# deck.net
KiCad netlist of a schematic drawn in EAGLE
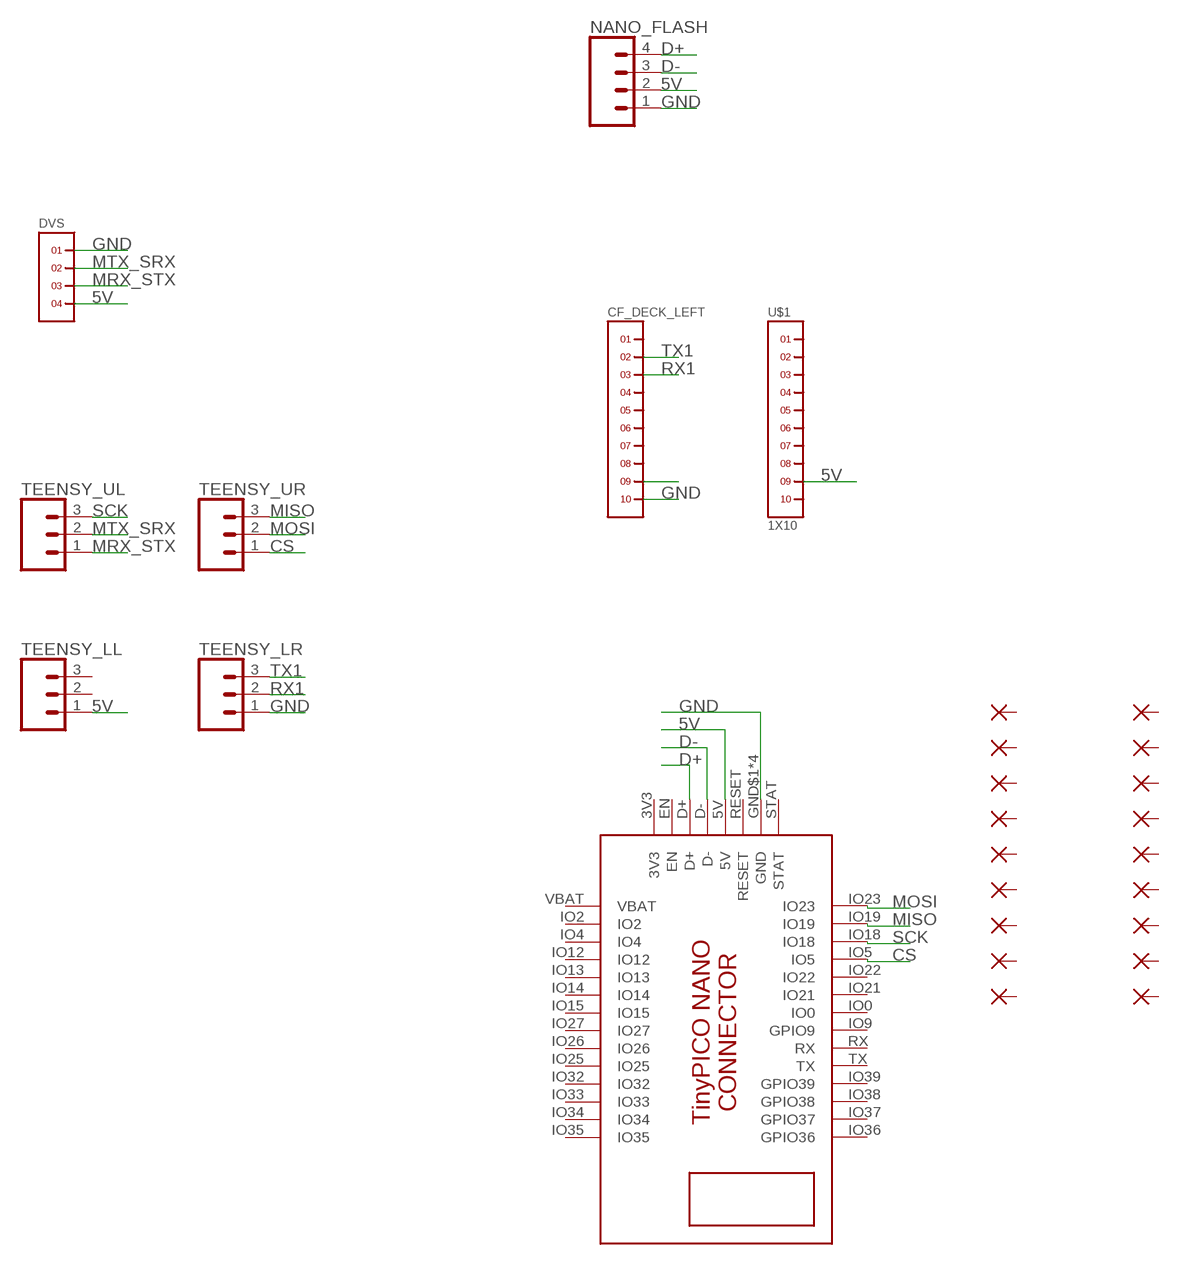
[diagram p0: schematic, sheet 1]

(export (version "E")
  (design (tool "Eeschema 10.0.6"))
  (components
    (comp (ref "CF_DECK_LEFT")
      (value "1X10")
      (footprint "eagle-import:1X10")
      (libsource (lib "eagle-import") (part "1X10"))
    )
    (comp (ref "DVS")
      (value "1X4")
      (footprint "eagle-import:1X4")
      (libsource (lib "eagle-import") (part "1X4"))
    )
    (comp (ref "NANO_FLASH")
      (value "CONN_041X04_NO_SILK")
      (footprint "eagle-import:1X04_NO_SILK")
      (libsource (lib "eagle-import") (part "CONN_041X04_NO_SILK"))
    )
    (comp (ref "PAD1")
      (value "SMD2")
      (footprint "eagle-import:SMD1,27-2,54")
      (libsource (lib "eagle-import") (part "SMD2"))
    )
    (comp (ref "PAD2")
      (value "SMD2")
      (footprint "eagle-import:SMD1,27-2,54")
      (libsource (lib "eagle-import") (part "SMD2"))
    )
    (comp (ref "PAD3")
      (value "SMD2")
      (footprint "eagle-import:SMD1,27-2,54")
      (libsource (lib "eagle-import") (part "SMD2"))
    )
    (comp (ref "PAD4")
      (value "SMD2")
      (footprint "eagle-import:SMD1,27-2,54")
      (libsource (lib "eagle-import") (part "SMD2"))
    )
    (comp (ref "PAD5")
      (value "SMD2")
      (footprint "eagle-import:SMD1,27-2,54")
      (libsource (lib "eagle-import") (part "SMD2"))
    )
    (comp (ref "PAD6")
      (value "SMD2")
      (footprint "eagle-import:SMD1,27-2,54")
      (libsource (lib "eagle-import") (part "SMD2"))
    )
    (comp (ref "PAD7")
      (value "SMD2")
      (footprint "eagle-import:SMD1,27-2,54")
      (libsource (lib "eagle-import") (part "SMD2"))
    )
    (comp (ref "PAD8")
      (value "SMD2")
      (footprint "eagle-import:SMD1,27-2,54")
      (libsource (lib "eagle-import") (part "SMD2"))
    )
    (comp (ref "PAD9")
      (value "SMD2")
      (footprint "eagle-import:SMD1,27-2,54")
      (libsource (lib "eagle-import") (part "SMD2"))
    )
    (comp (ref "PAD10")
      (value "SMD2")
      (footprint "eagle-import:SMD1,27-2,54")
      (libsource (lib "eagle-import") (part "SMD2"))
    )
    (comp (ref "PAD11")
      (value "SMD2")
      (footprint "eagle-import:SMD1,27-2,54")
      (libsource (lib "eagle-import") (part "SMD2"))
    )
    (comp (ref "PAD12")
      (value "SMD2")
      (footprint "eagle-import:SMD1,27-2,54")
      (libsource (lib "eagle-import") (part "SMD2"))
    )
    (comp (ref "PAD13")
      (value "SMD2")
      (footprint "eagle-import:SMD1,27-2,54")
      (libsource (lib "eagle-import") (part "SMD2"))
    )
    (comp (ref "PAD14")
      (value "SMD2")
      (footprint "eagle-import:SMD1,27-2,54")
      (libsource (lib "eagle-import") (part "SMD2"))
    )
    (comp (ref "PAD15")
      (value "SMD2")
      (footprint "eagle-import:SMD1,27-2,54")
      (libsource (lib "eagle-import") (part "SMD2"))
    )
    (comp (ref "PAD16")
      (value "SMD2")
      (footprint "eagle-import:SMD1,27-2,54")
      (libsource (lib "eagle-import") (part "SMD2"))
    )
    (comp (ref "PAD17")
      (value "SMD2")
      (footprint "eagle-import:SMD1,27-2,54")
      (libsource (lib "eagle-import") (part "SMD2"))
    )
    (comp (ref "PAD18")
      (value "SMD2")
      (footprint "eagle-import:SMD1,27-2,54")
      (libsource (lib "eagle-import") (part "SMD2"))
    )
    (comp (ref "TEENSY_LL")
      (value "CONN_031X03_NO_SILK")
      (footprint "eagle-import:1X03_NO_SILK")
      (libsource (lib "eagle-import") (part "CONN_031X03_NO_SILK"))
    )
    (comp (ref "TEENSY_LR")
      (value "CONN_031X03_NO_SILK")
      (footprint "eagle-import:1X03_NO_SILK")
      (libsource (lib "eagle-import") (part "CONN_031X03_NO_SILK"))
    )
    (comp (ref "TEENSY_UL")
      (value "CONN_031X03_NO_SILK")
      (footprint "eagle-import:1X03_NO_SILK")
      (libsource (lib "eagle-import") (part "CONN_031X03_NO_SILK"))
    )
    (comp (ref "TEENSY_UR")
      (value "CONN_031X03_NO_SILK")
      (footprint "eagle-import:1X03_NO_SILK")
      (libsource (lib "eagle-import") (part "CONN_031X03_NO_SILK"))
    )
    (comp (ref "U$1")
      (value "1X10")
      (footprint "eagle-import:1X10")
      (libsource (lib "eagle-import") (part "1X10"))
    )
    (comp (ref "U$4")
      (value "TINYPICO-NANO-CONNECTOR")
      (footprint "eagle-import:TINYPICO-NANO-CONNECTOR")
      (libsource (lib "eagle-import") (part "TINYPICO-NANO-CONNECTOR"))
    )
  )
  (nets
    (net (code "1") (name "/3V3") (class "Default")
      (node (ref "U$4") (pin "3V3") (pinfunction "3V3_3V3") (pintype "power_in"))
    )
    (net (code "2") (name "/5V") (class "Default")
      (node (ref "DVS") (pin "4") (pinfunction "4_4") (pintype "bidirectional"))
      (node (ref "NANO_FLASH") (pin "2") (pinfunction "2_2") (pintype "passive"))
      (node (ref "TEENSY_LL") (pin "1") (pinfunction "1_1") (pintype "passive"))
      (node (ref "U$1") (pin "9") (pinfunction "9_9") (pintype "bidirectional"))
      (node (ref "U$4") (pin "5V") (pinfunction "5V_5V") (pintype "power_in"))
    )
    (net (code "3") (name "/CS") (class "Default")
      (node (ref "TEENSY_UR") (pin "1") (pinfunction "1_1") (pintype "passive"))
      (node (ref "U$4") (pin "IO5") (pinfunction "IO5_IO5") (pintype "bidirectional"))
    )
    (net (code "4") (name "/D+") (class "Default")
      (node (ref "NANO_FLASH") (pin "4") (pinfunction "4_4") (pintype "passive"))
      (node (ref "U$4") (pin "D+") (pinfunction "D+_D+") (pintype "bidirectional"))
    )
    (net (code "5") (name "/D-") (class "Default")
      (node (ref "NANO_FLASH") (pin "3") (pinfunction "3_3") (pintype "passive"))
      (node (ref "U$4") (pin "D-") (pinfunction "D-_D-") (pintype "bidirectional"))
    )
    (net (code "6") (name "/GND") (class "Default")
      (node (ref "CF_DECK_LEFT") (pin "10") (pinfunction "10_10") (pintype "bidirectional"))
      (node (ref "DVS") (pin "1") (pinfunction "1_1") (pintype "bidirectional"))
      (node (ref "NANO_FLASH") (pin "1") (pinfunction "1_1") (pintype "passive"))
      (node (ref "TEENSY_LR") (pin "1") (pinfunction "1_1") (pintype "passive"))
      (node (ref "U$4") (pin "GND$1") (pinfunction "GND_GND$1") (pintype "power_in"))
      (node (ref "U$4") (pin "GND$2") (pinfunction "GND_GND$2") (pintype "power_in"))
      (node (ref "U$4") (pin "GND$3") (pinfunction "GND_GND$3") (pintype "power_in"))
      (node (ref "U$4") (pin "GND$4") (pinfunction "GND_GND$4") (pintype "power_in"))
    )
    (net (code "7") (name "/MISO") (class "Default")
      (node (ref "TEENSY_UR") (pin "3") (pinfunction "3_3") (pintype "passive"))
      (node (ref "U$4") (pin "IO19") (pinfunction "IO19_IO19") (pintype "bidirectional"))
    )
    (net (code "8") (name "/MOSI") (class "Default")
      (node (ref "TEENSY_UR") (pin "2") (pinfunction "2_2") (pintype "passive"))
      (node (ref "U$4") (pin "IO23") (pinfunction "IO23_IO23") (pintype "bidirectional"))
    )
    (net (code "9") (name "/MRX_STX") (class "Default")
      (node (ref "DVS") (pin "3") (pinfunction "3_3") (pintype "bidirectional"))
      (node (ref "TEENSY_UL") (pin "1") (pinfunction "1_1") (pintype "passive"))
    )
    (net (code "10") (name "/MTX_SRX") (class "Default")
      (node (ref "DVS") (pin "2") (pinfunction "2_2") (pintype "bidirectional"))
      (node (ref "TEENSY_UL") (pin "2") (pinfunction "2_2") (pintype "passive"))
    )
    (net (code "11") (name "/RX1") (class "Default")
      (node (ref "CF_DECK_LEFT") (pin "3") (pinfunction "3_3") (pintype "bidirectional"))
      (node (ref "TEENSY_LR") (pin "2") (pinfunction "2_2") (pintype "passive"))
    )
    (net (code "12") (name "/SCK") (class "Default")
      (node (ref "TEENSY_UL") (pin "3") (pinfunction "3_3") (pintype "passive"))
      (node (ref "U$4") (pin "IO18") (pinfunction "IO18_IO18") (pintype "bidirectional"))
    )
    (net (code "13") (name "/TX1") (class "Default")
      (node (ref "CF_DECK_LEFT") (pin "2") (pinfunction "2_2") (pintype "bidirectional"))
      (node (ref "TEENSY_LR") (pin "3") (pinfunction "3_3") (pintype "passive"))
    )
    (net (code "14") (name "/VBAT") (class "Default")
      (node (ref "U$4") (pin "VBAT") (pinfunction "VBAT_VBAT") (pintype "power_in"))
    )
    (net (code "15") (name "unconnected-(CF_DECK_LEFT-Pad1)") (class "Default")
      (node (ref "CF_DECK_LEFT") (pin "1") (pinfunction "1_1") (pintype "bidirectional"))
    )
    (net (code "16") (name "unconnected-(CF_DECK_LEFT-Pad4)") (class "Default")
      (node (ref "CF_DECK_LEFT") (pin "4") (pinfunction "4_4") (pintype "bidirectional"))
    )
    (net (code "17") (name "unconnected-(CF_DECK_LEFT-Pad5)") (class "Default")
      (node (ref "CF_DECK_LEFT") (pin "5") (pinfunction "5_5") (pintype "bidirectional"))
    )
    (net (code "18") (name "unconnected-(CF_DECK_LEFT-Pad6)") (class "Default")
      (node (ref "CF_DECK_LEFT") (pin "6") (pinfunction "6_6") (pintype "bidirectional"))
    )
    (net (code "19") (name "unconnected-(CF_DECK_LEFT-Pad7)") (class "Default")
      (node (ref "CF_DECK_LEFT") (pin "7") (pinfunction "7_7") (pintype "bidirectional"))
    )
    (net (code "20") (name "unconnected-(CF_DECK_LEFT-Pad8)") (class "Default")
      (node (ref "CF_DECK_LEFT") (pin "8") (pinfunction "8_8") (pintype "bidirectional"))
    )
    (net (code "21") (name "unconnected-(CF_DECK_LEFT-Pad9)") (class "Default")
      (node (ref "CF_DECK_LEFT") (pin "9") (pinfunction "9_9") (pintype "bidirectional"))
    )
    (net (code "22") (name "unconnected-(PAD1-P-Pad1)") (class "Default")
      (node (ref "PAD1") (pin "1") (pinfunction "P_1") (pintype "passive"))
    )
    (net (code "23") (name "unconnected-(PAD2-P-Pad1)") (class "Default")
      (node (ref "PAD2") (pin "1") (pinfunction "P_1") (pintype "passive"))
    )
    (net (code "24") (name "unconnected-(PAD3-P-Pad1)") (class "Default")
      (node (ref "PAD3") (pin "1") (pinfunction "P_1") (pintype "passive"))
    )
    (net (code "25") (name "unconnected-(PAD4-P-Pad1)") (class "Default")
      (node (ref "PAD4") (pin "1") (pinfunction "P_1") (pintype "passive"))
    )
    (net (code "26") (name "unconnected-(PAD5-P-Pad1)") (class "Default")
      (node (ref "PAD5") (pin "1") (pinfunction "P_1") (pintype "passive"))
    )
    (net (code "27") (name "unconnected-(PAD6-P-Pad1)") (class "Default")
      (node (ref "PAD6") (pin "1") (pinfunction "P_1") (pintype "passive"))
    )
    (net (code "28") (name "unconnected-(PAD7-P-Pad1)") (class "Default")
      (node (ref "PAD7") (pin "1") (pinfunction "P_1") (pintype "passive"))
    )
    (net (code "29") (name "unconnected-(PAD8-P-Pad1)") (class "Default")
      (node (ref "PAD8") (pin "1") (pinfunction "P_1") (pintype "passive"))
    )
    (net (code "30") (name "unconnected-(PAD9-P-Pad1)") (class "Default")
      (node (ref "PAD9") (pin "1") (pinfunction "P_1") (pintype "passive"))
    )
    (net (code "31") (name "unconnected-(PAD10-P-Pad1)") (class "Default")
      (node (ref "PAD10") (pin "1") (pinfunction "P_1") (pintype "passive"))
    )
    (net (code "32") (name "unconnected-(PAD11-P-Pad1)") (class "Default")
      (node (ref "PAD11") (pin "1") (pinfunction "P_1") (pintype "passive"))
    )
    (net (code "33") (name "unconnected-(PAD12-P-Pad1)") (class "Default")
      (node (ref "PAD12") (pin "1") (pinfunction "P_1") (pintype "passive"))
    )
    (net (code "34") (name "unconnected-(PAD13-P-Pad1)") (class "Default")
      (node (ref "PAD13") (pin "1") (pinfunction "P_1") (pintype "passive"))
    )
    (net (code "35") (name "unconnected-(PAD14-P-Pad1)") (class "Default")
      (node (ref "PAD14") (pin "1") (pinfunction "P_1") (pintype "passive"))
    )
    (net (code "36") (name "unconnected-(PAD15-P-Pad1)") (class "Default")
      (node (ref "PAD15") (pin "1") (pinfunction "P_1") (pintype "passive"))
    )
    (net (code "37") (name "unconnected-(PAD16-P-Pad1)") (class "Default")
      (node (ref "PAD16") (pin "1") (pinfunction "P_1") (pintype "passive"))
    )
    (net (code "38") (name "unconnected-(PAD17-P-Pad1)") (class "Default")
      (node (ref "PAD17") (pin "1") (pinfunction "P_1") (pintype "passive"))
    )
    (net (code "39") (name "unconnected-(PAD18-P-Pad1)") (class "Default")
      (node (ref "PAD18") (pin "1") (pinfunction "P_1") (pintype "passive"))
    )
    (net (code "40") (name "unconnected-(TEENSY_LL-Pad2)") (class "Default")
      (node (ref "TEENSY_LL") (pin "2") (pinfunction "2_2") (pintype "passive"))
    )
    (net (code "41") (name "unconnected-(TEENSY_LL-Pad3)") (class "Default")
      (node (ref "TEENSY_LL") (pin "3") (pinfunction "3_3") (pintype "passive"))
    )
    (net (code "42") (name "unconnected-(U$1-Pad1)") (class "Default")
      (node (ref "U$1") (pin "1") (pinfunction "1_1") (pintype "bidirectional"))
    )
    (net (code "43") (name "unconnected-(U$1-Pad2)") (class "Default")
      (node (ref "U$1") (pin "2") (pinfunction "2_2") (pintype "bidirectional"))
    )
    (net (code "44") (name "unconnected-(U$1-Pad3)") (class "Default")
      (node (ref "U$1") (pin "3") (pinfunction "3_3") (pintype "bidirectional"))
    )
    (net (code "45") (name "unconnected-(U$1-Pad4)") (class "Default")
      (node (ref "U$1") (pin "4") (pinfunction "4_4") (pintype "bidirectional"))
    )
    (net (code "46") (name "unconnected-(U$1-Pad5)") (class "Default")
      (node (ref "U$1") (pin "5") (pinfunction "5_5") (pintype "bidirectional"))
    )
    (net (code "47") (name "unconnected-(U$1-Pad6)") (class "Default")
      (node (ref "U$1") (pin "6") (pinfunction "6_6") (pintype "bidirectional"))
    )
    (net (code "48") (name "unconnected-(U$1-Pad7)") (class "Default")
      (node (ref "U$1") (pin "7") (pinfunction "7_7") (pintype "bidirectional"))
    )
    (net (code "49") (name "unconnected-(U$1-Pad8)") (class "Default")
      (node (ref "U$1") (pin "8") (pinfunction "8_8") (pintype "bidirectional"))
    )
    (net (code "50") (name "unconnected-(U$1-Pad10)") (class "Default")
      (node (ref "U$1") (pin "10") (pinfunction "10_10") (pintype "bidirectional"))
    )
    (net (code "51") (name "unconnected-(U$4-GPIO9-PadIO9)") (class "Default")
      (node (ref "U$4") (pin "IO9") (pinfunction "GPIO9_IO9") (pintype "bidirectional"))
    )
    (net (code "52") (name "unconnected-(U$4-GPIO36-PadIO36)") (class "Default")
      (node (ref "U$4") (pin "IO36") (pinfunction "GPIO36_IO36") (pintype "bidirectional"))
    )
    (net (code "53") (name "unconnected-(U$4-GPIO37-PadIO37)") (class "Default")
      (node (ref "U$4") (pin "IO37") (pinfunction "GPIO37_IO37") (pintype "bidirectional"))
    )
    (net (code "54") (name "unconnected-(U$4-GPIO38-PadIO38)") (class "Default")
      (node (ref "U$4") (pin "IO38") (pinfunction "GPIO38_IO38") (pintype "bidirectional"))
    )
    (net (code "55") (name "unconnected-(U$4-GPIO39-PadIO39)") (class "Default")
      (node (ref "U$4") (pin "IO39") (pinfunction "GPIO39_IO39") (pintype "bidirectional"))
    )
    (net (code "56") (name "unconnected-(U$4-PadEN)") (class "Default")
      (node (ref "U$4") (pin "EN") (pinfunction "EN_EN") (pintype "input"))
    )
    (net (code "57") (name "unconnected-(U$4-PadIO0)") (class "Default")
      (node (ref "U$4") (pin "IO0") (pinfunction "IO0_IO0") (pintype "bidirectional"))
    )
    (net (code "58") (name "unconnected-(U$4-PadIO2)") (class "Default")
      (node (ref "U$4") (pin "IO2") (pinfunction "IO2_IO2") (pintype "bidirectional"))
    )
    (net (code "59") (name "unconnected-(U$4-PadIO4)") (class "Default")
      (node (ref "U$4") (pin "IO4") (pinfunction "IO4_IO4") (pintype "bidirectional"))
    )
    (net (code "60") (name "unconnected-(U$4-PadIO12)") (class "Default")
      (node (ref "U$4") (pin "IO12") (pinfunction "IO12_IO12") (pintype "bidirectional"))
    )
    (net (code "61") (name "unconnected-(U$4-PadIO13)") (class "Default")
      (node (ref "U$4") (pin "IO13") (pinfunction "IO13_IO13") (pintype "bidirectional"))
    )
    (net (code "62") (name "unconnected-(U$4-PadIO14)") (class "Default")
      (node (ref "U$4") (pin "IO14") (pinfunction "IO14_IO14") (pintype "bidirectional"))
    )
    (net (code "63") (name "unconnected-(U$4-PadIO15)") (class "Default")
      (node (ref "U$4") (pin "IO15") (pinfunction "IO15_IO15") (pintype "bidirectional"))
    )
    (net (code "64") (name "unconnected-(U$4-PadIO21)") (class "Default")
      (node (ref "U$4") (pin "IO21") (pinfunction "IO21_IO21") (pintype "bidirectional"))
    )
    (net (code "65") (name "unconnected-(U$4-PadIO22)") (class "Default")
      (node (ref "U$4") (pin "IO22") (pinfunction "IO22_IO22") (pintype "bidirectional"))
    )
    (net (code "66") (name "unconnected-(U$4-PadIO25)") (class "Default")
      (node (ref "U$4") (pin "IO25") (pinfunction "IO25_IO25") (pintype "bidirectional"))
    )
    (net (code "67") (name "unconnected-(U$4-PadIO26)") (class "Default")
      (node (ref "U$4") (pin "IO26") (pinfunction "IO26_IO26") (pintype "bidirectional"))
    )
    (net (code "68") (name "unconnected-(U$4-PadIO27)") (class "Default")
      (node (ref "U$4") (pin "IO27") (pinfunction "IO27_IO27") (pintype "bidirectional"))
    )
    (net (code "69") (name "unconnected-(U$4-PadIO32)") (class "Default")
      (node (ref "U$4") (pin "IO32") (pinfunction "IO32_IO32") (pintype "bidirectional"))
    )
    (net (code "70") (name "unconnected-(U$4-PadIO33)") (class "Default")
      (node (ref "U$4") (pin "IO33") (pinfunction "IO33_IO33") (pintype "bidirectional"))
    )
    (net (code "71") (name "unconnected-(U$4-PadIO34)") (class "Default")
      (node (ref "U$4") (pin "IO34") (pinfunction "IO34_IO34") (pintype "bidirectional"))
    )
    (net (code "72") (name "unconnected-(U$4-PadIO35)") (class "Default")
      (node (ref "U$4") (pin "IO35") (pinfunction "IO35_IO35") (pintype "bidirectional"))
    )
    (net (code "73") (name "unconnected-(U$4-PadRESET)") (class "Default")
      (node (ref "U$4") (pin "RESET") (pinfunction "RESET_RESET") (pintype "bidirectional"))
    )
    (net (code "74") (name "unconnected-(U$4-PadRX)") (class "Default")
      (node (ref "U$4") (pin "RX") (pinfunction "RX_RX") (pintype "bidirectional"))
    )
    (net (code "75") (name "unconnected-(U$4-PadSTAT)") (class "Default")
      (node (ref "U$4") (pin "STAT") (pinfunction "STAT_STAT") (pintype "output"))
    )
    (net (code "76") (name "unconnected-(U$4-PadTX)") (class "Default")
      (node (ref "U$4") (pin "TX") (pinfunction "TX_TX") (pintype "bidirectional"))
    )
  )
)
